# STM32_JBL_02.net
KiCad netlist of a schematic drawn in EasyEDA Pro
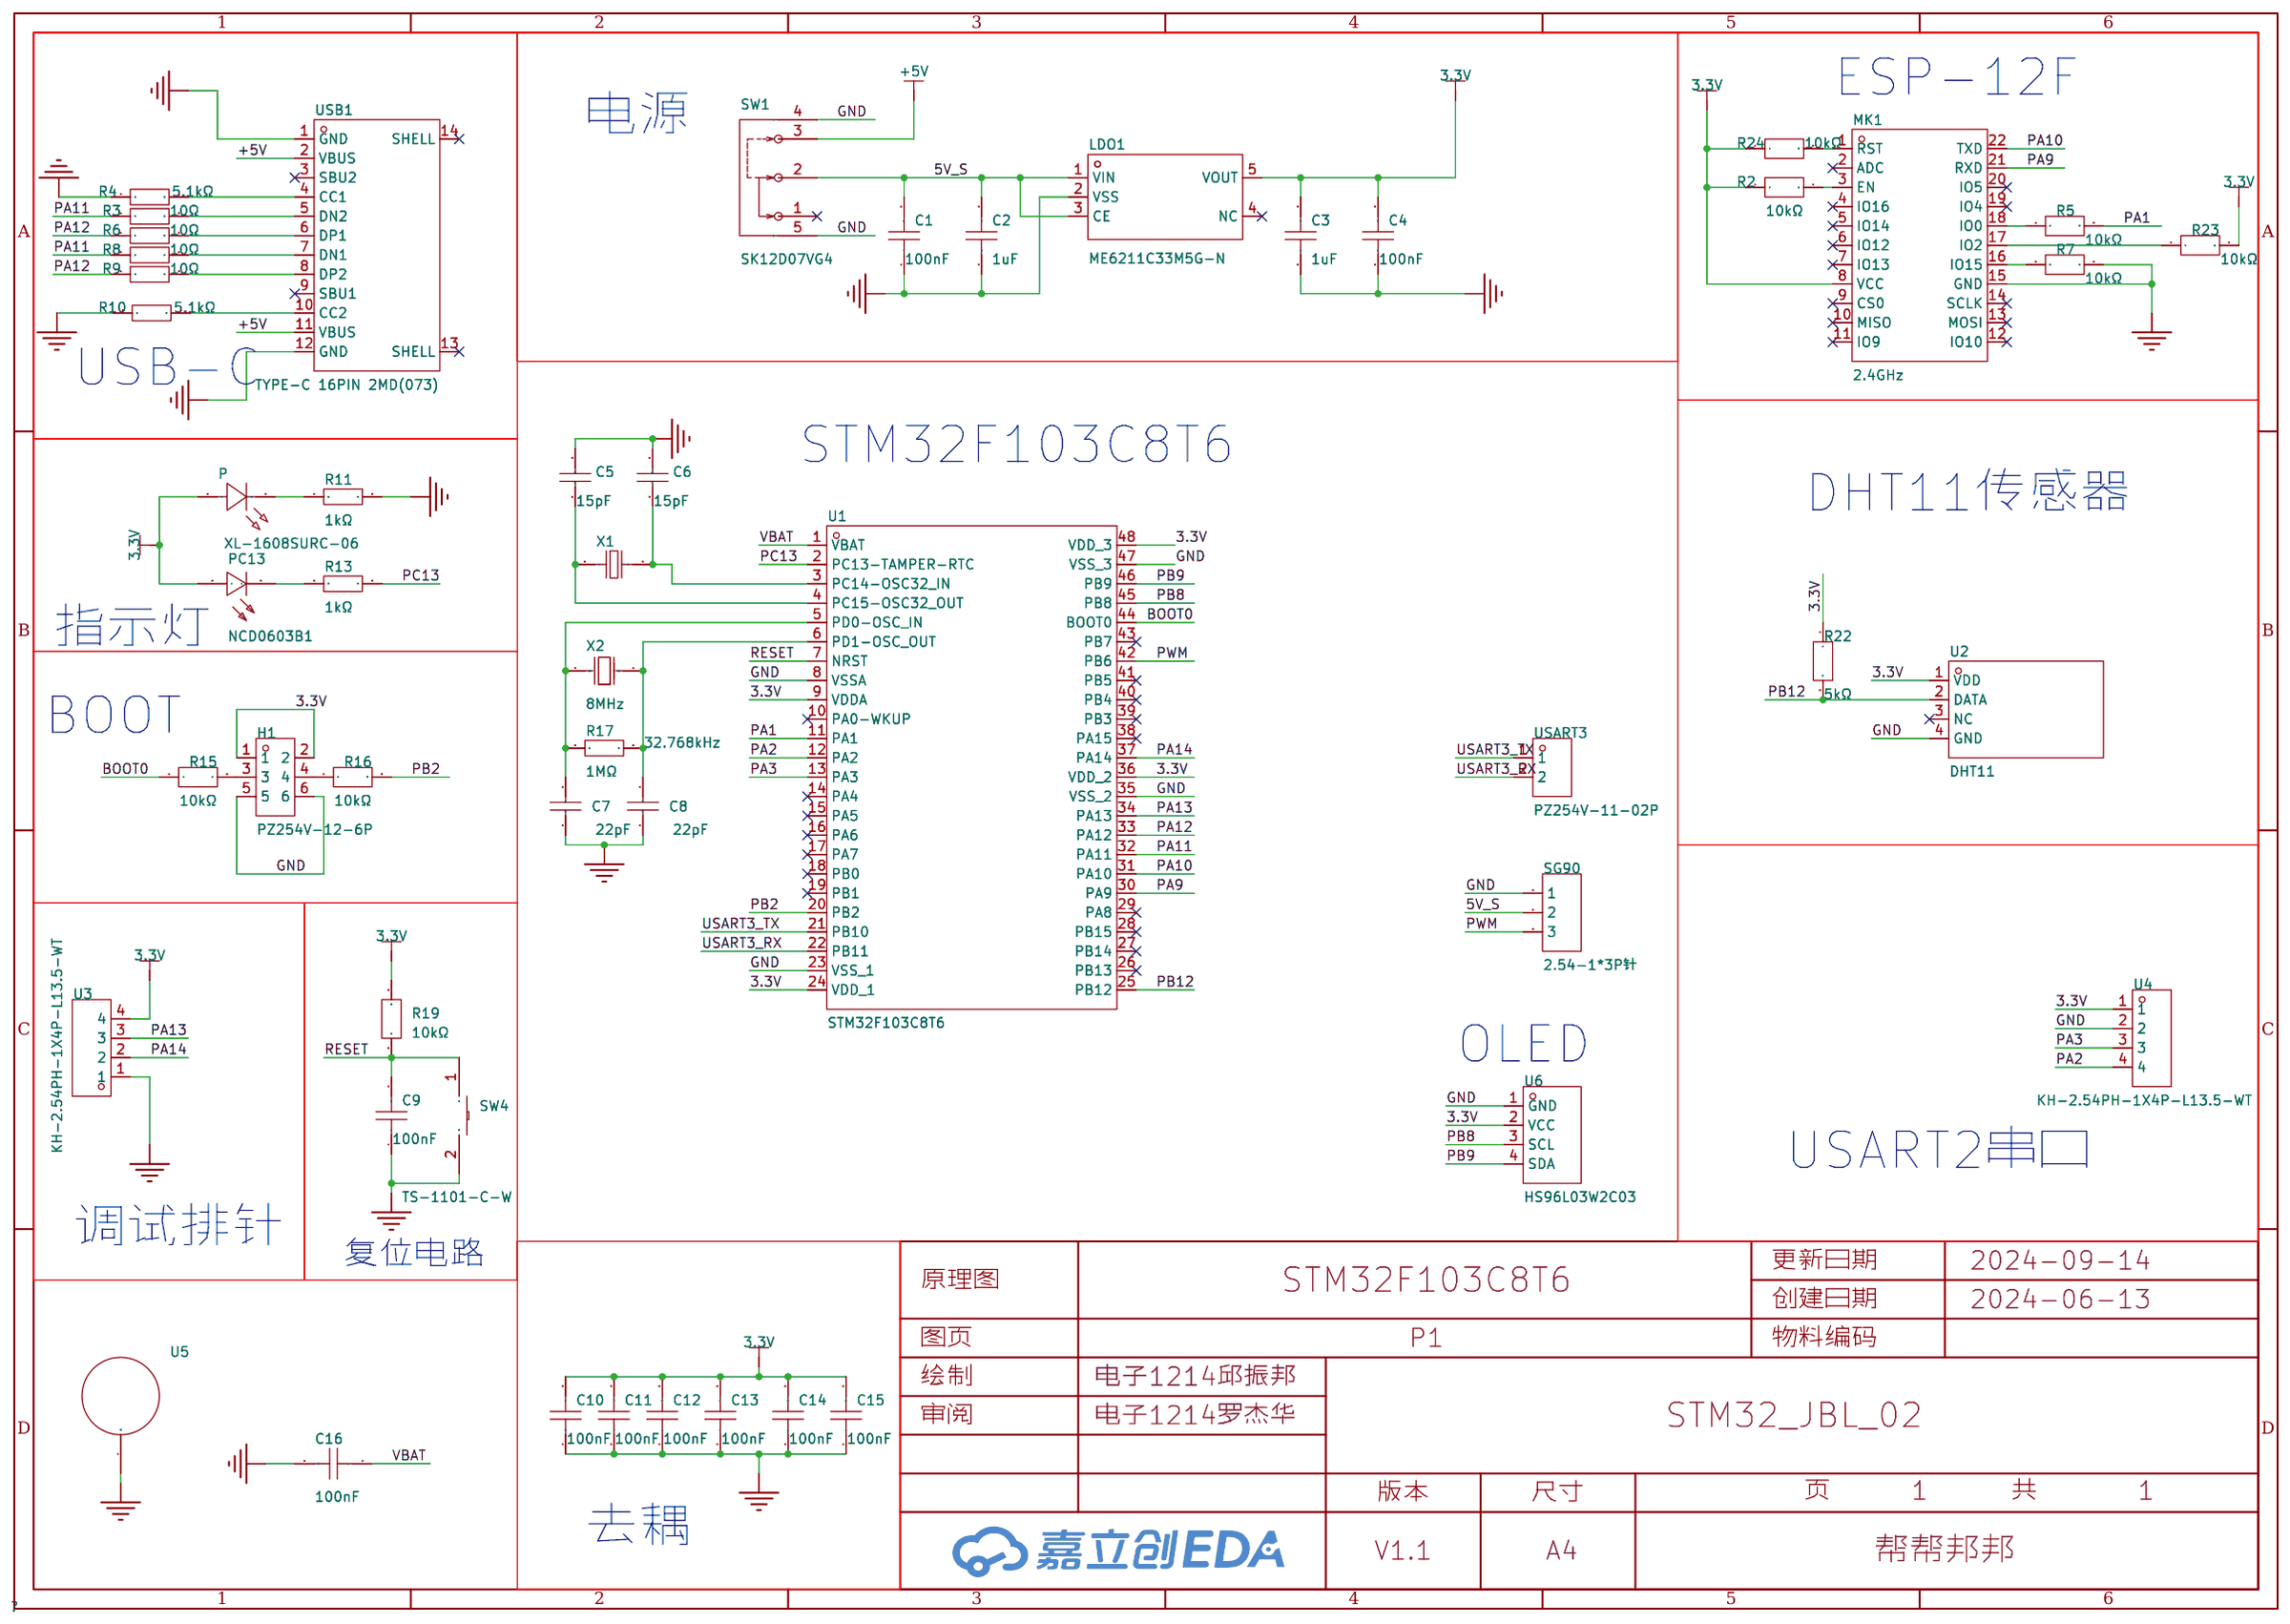
[diagram p0: schematic sheet]

(export (version "E")
  (design (tool "Eeschema 10.0.6"))
  (components
    (comp (ref "C1")
      (value "100nF")
      (footprint "easyedapro:C0603")
      (description "容值:100nF;精度:±10%;额定电压:50V;材质(温度系数):X7R;")
      (fields
        (field (name "Manufacturer Part") "CC0603KRX7R9BB104")
        (field (name "Manufacturer") "YAGEO(国巨)")
      )
      (libsource (lib "easyedapro") (part "CC0603KRX7R9BB104"))
    )
    (comp (ref "C2")
      (value "1uF")
      (footprint "easyedapro:C0603")
      (description "容值:1uF;精度:±10%;额定电压:50V;材质(温度系数):X5R;")
      (fields
        (field (name "Manufacturer Part") "CL10A105KB8NNNC")
        (field (name "Manufacturer") "SAMSUNG(三星)")
      )
      (libsource (lib "easyedapro") (part "CL10A105KB8NNNC"))
    )
    (comp (ref "C3")
      (value "1uF")
      (footprint "easyedapro:C0603")
      (description "容值:1uF;精度:±10%;额定电压:50V;材质(温度系数):X5R;")
      (fields
        (field (name "Manufacturer Part") "CL10A105KB8NNNC")
        (field (name "Manufacturer") "SAMSUNG(三星)")
      )
      (libsource (lib "easyedapro") (part "CL10A105KB8NNNC"))
    )
    (comp (ref "C4")
      (value "100nF")
      (footprint "easyedapro:C0603")
      (description "容值:100nF;精度:±10%;额定电压:50V;材质(温度系数):X7R;")
      (fields
        (field (name "Manufacturer Part") "CC0603KRX7R9BB104")
        (field (name "Manufacturer") "YAGEO(国巨)")
      )
      (libsource (lib "easyedapro") (part "CC0603KRX7R9BB104"))
    )
    (comp (ref "C5")
      (value "15pF")
      (footprint "easyedapro:C0603")
      (description "容值:15pF;精度:±5%;额定电压:50V;材质(温度系数):C0G;")
      (fields
        (field (name "Manufacturer Part") "CL10C150JB8NNNC")
        (field (name "Manufacturer") "SAMSUNG(三星)")
      )
      (libsource (lib "easyedapro") (part "CL10C150JB8NNNC"))
    )
    (comp (ref "C6")
      (value "15pF")
      (footprint "easyedapro:C0603")
      (description "容值:15pF;精度:±5%;额定电压:50V;材质(温度系数):C0G;")
      (fields
        (field (name "Manufacturer Part") "CL10C150JB8NNNC")
        (field (name "Manufacturer") "SAMSUNG(三星)")
      )
      (libsource (lib "easyedapro") (part "CL10C150JB8NNNC"))
    )
    (comp (ref "C7")
      (value "22pF")
      (footprint "easyedapro:C0603")
      (description "容值:22pF;精度:±5%;额定电压:50V;材质(温度系数):NP0;")
      (fields
        (field (name "Manufacturer Part") "CC0603JRNPO9BN220")
        (field (name "Manufacturer") "YAGEO(国巨)")
      )
      (libsource (lib "easyedapro") (part "CC0603JRNPO9BN220"))
    )
    (comp (ref "C8")
      (value "22pF")
      (footprint "easyedapro:C0603")
      (description "容值:22pF;精度:±5%;额定电压:50V;材质(温度系数):NP0;")
      (fields
        (field (name "Manufacturer Part") "CC0603JRNPO9BN220")
        (field (name "Manufacturer") "YAGEO(国巨)")
      )
      (libsource (lib "easyedapro") (part "CC0603JRNPO9BN220"))
    )
    (comp (ref "C9")
      (value "100nF")
      (footprint "easyedapro:C0603")
      (description "容值:100nF;精度:±10%;额定电压:50V;材质(温度系数):X7R;")
      (fields
        (field (name "Manufacturer Part") "CC0603KRX7R9BB104")
        (field (name "Manufacturer") "YAGEO(国巨)")
      )
      (libsource (lib "easyedapro") (part "CC0603KRX7R9BB104"))
    )
    (comp (ref "C10")
      (value "100nF")
      (footprint "easyedapro:C0603")
      (description "容值:100nF;精度:±10%;额定电压:50V;材质(温度系数):X7R;")
      (fields
        (field (name "Manufacturer Part") "CC0603KRX7R9BB104")
        (field (name "Manufacturer") "YAGEO(国巨)")
      )
      (libsource (lib "easyedapro") (part "CC0603KRX7R9BB104"))
    )
    (comp (ref "C11")
      (value "100nF")
      (footprint "easyedapro:C0603")
      (description "容值:100nF;精度:±10%;额定电压:50V;材质(温度系数):X7R;")
      (fields
        (field (name "Manufacturer Part") "CC0603KRX7R9BB104")
        (field (name "Manufacturer") "YAGEO(国巨)")
      )
      (libsource (lib "easyedapro") (part "CC0603KRX7R9BB104"))
    )
    (comp (ref "C12")
      (value "100nF")
      (footprint "easyedapro:C0603")
      (description "容值:100nF;精度:±10%;额定电压:50V;材质(温度系数):X7R;")
      (fields
        (field (name "Manufacturer Part") "CC0603KRX7R9BB104")
        (field (name "Manufacturer") "YAGEO(国巨)")
      )
      (libsource (lib "easyedapro") (part "CC0603KRX7R9BB104"))
    )
    (comp (ref "C13")
      (value "100nF")
      (footprint "easyedapro:C0603")
      (description "容值:100nF;精度:±10%;额定电压:50V;材质(温度系数):X7R;")
      (fields
        (field (name "Manufacturer Part") "CC0603KRX7R9BB104")
        (field (name "Manufacturer") "YAGEO(国巨)")
      )
      (libsource (lib "easyedapro") (part "CC0603KRX7R9BB104"))
    )
    (comp (ref "C14")
      (value "100nF")
      (footprint "easyedapro:C0603")
      (description "容值:100nF;精度:±10%;额定电压:50V;材质(温度系数):X7R;")
      (fields
        (field (name "Manufacturer Part") "CC0603KRX7R9BB104")
        (field (name "Manufacturer") "YAGEO(国巨)")
      )
      (libsource (lib "easyedapro") (part "CC0603KRX7R9BB104"))
    )
    (comp (ref "C15")
      (value "100nF")
      (footprint "easyedapro:C0603")
      (description "容值:100nF;精度:±10%;额定电压:50V;材质(温度系数):X7R;")
      (fields
        (field (name "Manufacturer Part") "CC0603KRX7R9BB104")
        (field (name "Manufacturer") "YAGEO(国巨)")
      )
      (libsource (lib "easyedapro") (part "CC0603KRX7R9BB104"))
    )
    (comp (ref "C16")
      (value "100nF")
      (footprint "easyedapro:C0603")
      (description "容值:100nF;精度:±10%;额定电压:50V;材质(温度系数):X7R;")
      (fields
        (field (name "Manufacturer Part") "CC0603KRX7R9BB104")
        (field (name "Manufacturer") "YAGEO(国巨)")
      )
      (libsource (lib "easyedapro") (part "CC0603KRX7R9BB104"))
    )
    (comp (ref "H1")
      (value "PZ254V-12-6P")
      (footprint "easyedapro:HDR-TH_6P-P2.54-V-M-R2-C3-S2.54")
      (fields (field (name "Manufacturer") "XFCN(兴飞)"))
      (libsource (lib "easyedapro") (part "PZ254V-12-6P"))
    )
    (comp (ref "LDO1")
      (value "ME6211C33M5G-N")
      (footprint "easyedapro:SOT-23-5_L3.0-W1.7-P0.95-LS2.8-BL")
      (description "输出类型:固定;最大输入电压:6V;输出电压:3.3V;最大输出电流:500mA;电源纹波抑制比(PSRR):70dB;输出极性:正极;")
      (fields (field (name "Manufacturer") "MICRONE(南京微盟)"))
      (libsource (lib "easyedapro") (part "ME6211C33M5G-N"))
    )
    (comp (ref "MK1")
      (value "2.4GHz")
      (footprint "easyedapro:WIFIM-SMD_ESP-12E-BR")
      (description "核心处理器:ESP8266芯片;频率:2.4GHz;天线形式:板载PCB天线;发射功率:16dBm;接收灵敏度:-90dBm;")
      (fields (field (name "Manufacturer Part") "ESP-12E") (field (name "Manufacturer") "Ai-Thinker(安信可)"))
      (libsource (lib "easyedapro") (part "ESP-12E"))
    )
    (comp (ref "P")
      (value "XL-1608SURC-06")
      (footprint "easyedapro:LED0603-RD_RED")
      (description "发光颜色:红色;功率:55mW;正向电流:25mA;主波长:617nm~621nm;透镜颜色:无色透明透镜;色温:-;发光角度:120°;载带方式:正贴;工作温度:-30℃~+85℃;")
      (fields (field (name "Manufacturer") "XINGLIGHT(成兴光)"))
      (libsource (lib "easyedapro") (part "XL-1608SURC-06"))
    )
    (comp (ref "PC13")
      (value "NCD0603B1")
      (footprint "easyedapro:LED0603-RD")
      (fields (field (name "Manufacturer") "国星光电"))
      (libsource (lib "easyedapro") (part "FC-DA1608BK-470H10"))
    )
    (comp (ref "R2")
      (value "10kΩ")
      (footprint "easyedapro:R0603")
      (description "电阻类型:厚膜电阻;阻值:10kΩ;精度:±5%;功率:100mW;最大工作电压:75V;温度系数:±100ppm/°C;")
      (fields (field (name "Manufacturer Part") "FRC0603J103TS") (field (name "Manufacturer") "FOJAN(富捷)"))
      (libsource (lib "easyedapro") (part "FRC0603J103TS"))
    )
    (comp (ref "R3")
      (value "10Ω")
      (footprint "easyedapro:R0603")
      (description "电阻类型:厚膜电阻;阻值:10Ω;精度:±1%;功率:100mW;最大工作电压:75V;温度系数:±400ppm/°C;")
      (fields
        (field (name "Manufacturer Part") "0603WAF100JT5E")
        (field (name "Manufacturer") "UNI-ROYAL(厚声)")
      )
      (libsource (lib "easyedapro") (part "0603WAF100JT5E"))
    )
    (comp (ref "R4")
      (value "5.1kΩ")
      (footprint "easyedapro:R0603")
      (description "电阻类型:厚膜电阻;阻值:5.1kΩ;精度:±1%;功率:100mW;最大工作电压:75V;温度系数:±100ppm/°C;")
      (fields
        (field (name "Manufacturer Part") "0603WAF5101T5E")
        (field (name "Manufacturer") "UNI-ROYAL(厚声)")
      )
      (libsource (lib "easyedapro") (part "0603WAF5101T5E"))
    )
    (comp (ref "R5")
      (value "10kΩ")
      (footprint "easyedapro:R0603")
      (description "电阻类型:厚膜电阻;阻值:10kΩ;精度:±5%;功率:100mW;最大工作电压:75V;温度系数:±100ppm/°C;")
      (fields (field (name "Manufacturer Part") "FRC0603J103TS") (field (name "Manufacturer") "FOJAN(富捷)"))
      (libsource (lib "easyedapro") (part "FRC0603J103TS"))
    )
    (comp (ref "R6")
      (value "10Ω")
      (footprint "easyedapro:R0603")
      (description "电阻类型:厚膜电阻;阻值:10Ω;精度:±1%;功率:100mW;最大工作电压:75V;温度系数:±400ppm/°C;")
      (fields
        (field (name "Manufacturer Part") "0603WAF100JT5E")
        (field (name "Manufacturer") "UNI-ROYAL(厚声)")
      )
      (libsource (lib "easyedapro") (part "0603WAF100JT5E"))
    )
    (comp (ref "R7")
      (value "10kΩ")
      (footprint "easyedapro:R0603")
      (description "电阻类型:厚膜电阻;阻值:10kΩ;精度:±5%;功率:100mW;最大工作电压:75V;温度系数:±100ppm/°C;")
      (fields (field (name "Manufacturer Part") "FRC0603J103TS") (field (name "Manufacturer") "FOJAN(富捷)"))
      (libsource (lib "easyedapro") (part "FRC0603J103TS"))
    )
    (comp (ref "R8")
      (value "10Ω")
      (footprint "easyedapro:R0603")
      (description "电阻类型:厚膜电阻;阻值:10Ω;精度:±1%;功率:100mW;最大工作电压:75V;温度系数:±400ppm/°C;")
      (fields
        (field (name "Manufacturer Part") "0603WAF100JT5E")
        (field (name "Manufacturer") "UNI-ROYAL(厚声)")
      )
      (libsource (lib "easyedapro") (part "0603WAF100JT5E"))
    )
    (comp (ref "R9")
      (value "10Ω")
      (footprint "easyedapro:R0603")
      (description "电阻类型:厚膜电阻;阻值:10Ω;精度:±1%;功率:100mW;最大工作电压:75V;温度系数:±400ppm/°C;")
      (fields
        (field (name "Manufacturer Part") "0603WAF100JT5E")
        (field (name "Manufacturer") "UNI-ROYAL(厚声)")
      )
      (libsource (lib "easyedapro") (part "0603WAF100JT5E"))
    )
    (comp (ref "R10")
      (value "5.1kΩ")
      (footprint "easyedapro:R0603")
      (description "电阻类型:厚膜电阻;阻值:5.1kΩ;精度:±1%;功率:100mW;最大工作电压:75V;温度系数:±100ppm/°C;")
      (fields
        (field (name "Manufacturer Part") "0603WAF5101T5E")
        (field (name "Manufacturer") "UNI-ROYAL(厚声)")
      )
      (libsource (lib "easyedapro") (part "0603WAF5101T5E"))
    )
    (comp (ref "R11")
      (value "1kΩ")
      (footprint "easyedapro:R0603")
      (description "电阻类型:厚膜电阻;阻值:1kΩ;精度:±1%;功率:100mW;最大工作电压:75V;温度系数:±100ppm/°C;")
      (fields (field (name "Manufacturer Part") "RC0603FR-071KL") (field (name "Manufacturer") "YAGEO(国巨)"))
      (libsource (lib "easyedapro") (part "RC0603FR-071KL"))
    )
    (comp (ref "R13")
      (value "1kΩ")
      (footprint "easyedapro:R0603")
      (description "电阻类型:厚膜电阻;阻值:1kΩ;精度:±1%;功率:100mW;最大工作电压:75V;温度系数:±100ppm/°C;")
      (fields (field (name "Manufacturer Part") "RC0603FR-071KL") (field (name "Manufacturer") "YAGEO(国巨)"))
      (libsource (lib "easyedapro") (part "RC0603FR-071KL"))
    )
    (comp (ref "R15")
      (value "10kΩ")
      (footprint "easyedapro:R0603")
      (description "电阻类型:厚膜电阻;阻值:10kΩ;精度:±5%;功率:100mW;最大工作电压:75V;温度系数:±100ppm/°C;")
      (fields (field (name "Manufacturer Part") "FRC0603J103TS") (field (name "Manufacturer") "FOJAN(富捷)"))
      (libsource (lib "easyedapro") (part "FRC0603J103TS"))
    )
    (comp (ref "R16")
      (value "10kΩ")
      (footprint "easyedapro:R0603")
      (description "电阻类型:厚膜电阻;阻值:10kΩ;精度:±5%;功率:100mW;最大工作电压:75V;温度系数:±100ppm/°C;")
      (fields (field (name "Manufacturer Part") "FRC0603J103TS") (field (name "Manufacturer") "FOJAN(富捷)"))
      (libsource (lib "easyedapro") (part "FRC0603J103TS"))
    )
    (comp (ref "R17")
      (value "1MΩ")
      (footprint "easyedapro:R0603")
      (description "电阻类型:厚膜电阻;阻值:1MΩ;精度:±1%;功率:100mW;最大工作电压:75V;温度系数:±100ppm/°C;")
      (fields
        (field (name "Manufacturer Part") "0603WAF1004T5E")
        (field (name "Manufacturer") "UNI-ROYAL(厚声)")
      )
      (libsource (lib "easyedapro") (part "0603WAF1004T5E"))
    )
    (comp (ref "R19")
      (value "10kΩ")
      (footprint "easyedapro:R0603")
      (description "电阻类型:厚膜电阻;阻值:10kΩ;精度:±5%;功率:100mW;最大工作电压:75V;温度系数:±100ppm/℃;")
      (fields (field (name "Manufacturer Part") "FRC0603J103TS") (field (name "Manufacturer") "FOJAN(富捷)"))
      (libsource (lib "easyedapro") (part "FRC0603J103TS"))
    )
    (comp (ref "R22")
      (value "5kΩ")
      (footprint "easyedapro:R0805")
      (description "电阻类型:薄膜电阻;阻值:5kΩ;精度:±0.1%;功率:125mW;最大工作电压:150V;温度系数:±25ppm/℃;")
      (fields (field (name "Manufacturer Part") "ARG05BTC5001N") (field (name "Manufacturer") "Viking(光颉)"))
      (libsource (lib "easyedapro") (part "ARG05BTC5001N"))
    )
    (comp (ref "R23")
      (value "10kΩ")
      (footprint "easyedapro:R0603")
      (description "电阻类型:厚膜电阻;阻值:10kΩ;精度:±5%;功率:100mW;最大工作电压:75V;温度系数:±100ppm/°C;")
      (fields (field (name "Manufacturer Part") "FRC0603J103TS") (field (name "Manufacturer") "FOJAN(富捷)"))
      (libsource (lib "easyedapro") (part "FRC0603J103TS"))
    )
    (comp (ref "R24")
      (value "10kΩ")
      (footprint "easyedapro:R0603")
      (description "电阻类型:厚膜电阻;阻值:10kΩ;精度:±5%;功率:100mW;最大工作电压:75V;温度系数:±100ppm/°C;")
      (fields (field (name "Manufacturer Part") "FRC0603J103TS") (field (name "Manufacturer") "FOJAN(富捷)"))
      (libsource (lib "easyedapro") (part "FRC0603J103TS"))
    )
    (comp (ref "SG90")
      (value "2.54-1*3P针")
      (footprint "easyedapro:HDR-TH_3P-P2.54-V-M-1")
      (fields (field (name "Manufacturer") "BOOMELE(博穆精密)"))
      (libsource (lib "easyedapro") (part "Header-Male-2.54_1x3"))
    )
    (comp (ref "SW1")
      (value "SK12D07VG4")
      (footprint "easyedapro:SW-TH_SK12D07VG4")
      (description "电路结构:单刀双掷;安装方式:-;额定电流(DC):500mA;额定电压(DC):50V;额定电流(AC):-;额定电压(AC):-;机械寿命:5千次;")
      (fields (field (name "Manufacturer") "SHOU HAN(首韩)"))
      (libsource (lib "easyedapro") (part "SK12D07VG4"))
    )
    (comp (ref "SW4")
      (value "TS-1101-C-W")
      (footprint "easyedapro:SW-SMD_L6.0-W3.3-LS8.0")
      (fields (field (name "Manufacturer") "XKB Connectivity(中国星坤)"))
      (libsource (lib "easyedapro") (part "TS-1101-C-W"))
    )
    (comp (ref "U1")
      (value "STM32F103C8T6")
      (footprint "easyedapro:LQFP-48_L7.0-W7.0-P0.50-LS9.0-BL")
      (description "CPU内核:ARM-M3;程序存储容量:64KB;RAM总容量:20KB;GPIO端口数量:37;工作电压范围:2V~3.6V;CPU最大主频:72MHz;程序存储器类型:FLASH;")
      (fields (field (name "Manufacturer") "ST(意法半导体)"))
      (libsource (lib "easyedapro") (part "STM32F103C8T6"))
    )
    (comp (ref "U2")
      (value "DHT11")
      (footprint "easyedapro:SENSOR-TH_DHT11")
      (description "新款电容式数字温湿度传感器,老款已停产16.1x12.6x5.8mm")
      (fields (field (name "Manufacturer") "广州奥松"))
      (libsource (lib "easyedapro") (part "DHT11"))
    )
    (comp (ref "U3")
      (value "KH-2.54PH-1X4P-L13.5-WT")
      (footprint "easyedapro:HDR-SMD_4P-P2.54-H-M-W13.3-N")
      (description "插针结构:1x4P;间距:2.54mm;安装类型:卧贴;排数:单排;")
      (fields (field (name "Manufacturer") "kinghelm(金航标)"))
      (libsource (lib "easyedapro") (part "KH-2.54PH-1X4P-L13.5-WT"))
    )
    (comp (ref "U4")
      (value "KH-2.54PH-1X4P-L13.5-WT")
      (footprint "easyedapro:HDR-SMD_4P-P2.54-H-M-W13.3-N")
      (description "插针结构:1x4P;间距:2.54mm;安装类型:卧贴;排数:单排;")
      (fields (field (name "Manufacturer") "kinghelm(金航标)"))
      (libsource (lib "easyedapro") (part "KH-2.54PH-1X4P-L13.5-WT"))
    )
    (comp (ref "U5")
      (value "~")
      (footprint "easyedapro:定位孔")
      (description "定位孔")
      (libsource (lib "easyedapro") (part "定位孔"))
    )
    (comp (ref "U6")
      (value "HS96L03W2C03")
      (footprint "easyedapro:OLED-TH_L27.8-W27.2-P2.54_C9900033791")
      (description "主控芯片:SSD1315;接口类型:I2C;尺寸(inch):0.96;像素分辨率:128x64;")
      (fields (field (name "Manufacturer") "HS(汉昇)"))
      (libsource (lib "easyedapro") (part "HS96L03W2C03"))
    )
    (comp (ref "USART3")
      (value "PZ254V-11-02P")
      (footprint "easyedapro:HDR-TH_2P-P2.54-V-M")
      (fields (field (name "Manufacturer") "XFCN(兴飞)"))
      (libsource (lib "easyedapro") (part "PZ254V-11-02P"))
    )
    (comp (ref "USB1")
      (value "TYPE-C 16PIN 2MD(073)")
      (footprint "easyedapro:USB-C-SMD_TYPE-C-6PIN-2MD-073")
      (description "连接器类型:Type-C;标准:-;公母:母;端口数量:1;触点数量:16P;安装方式:卧贴;额定电流 - 电源:5A;工作温度范围:-25°C~+85°C;")
      (fields (field (name "Manufacturer") "SHOU HAN(首韩)"))
      (libsource (lib "easyedapro") (part "TYPE-C 16PIN 2MD(073)"))
    )
    (comp (ref "X1")
      (value "32.768kHz")
      (footprint "easyedapro:FC-135R_L3.2-W1.5")
      (description "晶振类型:贴片晶振;频率:32.768kHz;常温频差:±20ppm;外接负载电容:12.5pF;")
      (fields (field (name "Manufacturer Part") "Q13FC13500004") (field (name "Manufacturer") "EPSON(爱普生)"))
      (libsource (lib "easyedapro") (part "Q13FC1350000400"))
    )
    (comp (ref "X2")
      (value "8MHz")
      (footprint "easyedapro:CRYSTAL-SMD_L11.5-W4.8-LS12.7")
      (description "晶振类型:贴片晶振;频率:8MHz;常温频差:±20ppm;外接负载电容:20pF;频率稳定度(全温):±30ppm;")
      (fields (field (name "Manufacturer Part") "X49SM8MSD2SC") (field (name "Manufacturer") "YXC(扬兴晶振)"))
      (libsource (lib "easyedapro") (part "X49SM8MSD2SC"))
    )
  )
  (nets
    (net (code "1") (name "+5V") (class "Default")
      (node (ref "SW1") (pin "3") (pinfunction "3_3") (pintype "unspecified"))
      (node (ref "USB1") (pin "11") (pinfunction "VBUS_11") (pintype "unspecified"))
      (node (ref "USB1") (pin "2") (pinfunction "VBUS_2") (pintype "unspecified"))
    )
    (net (code "2") (name "/5V_S") (class "Default")
      (node (ref "C1") (pin "2") (pinfunction "2_2") (pintype "unspecified"))
      (node (ref "C2") (pin "2") (pinfunction "2_2") (pintype "unspecified"))
      (node (ref "LDO1") (pin "1") (pinfunction "VIN_1") (pintype "input"))
      (node (ref "LDO1") (pin "3") (pinfunction "CE_3") (pintype "input"))
      (node (ref "SG90") (pin "2") (pinfunction "2_2") (pintype "input"))
      (node (ref "SW1") (pin "2") (pinfunction "2_2") (pintype "unspecified"))
    )
    (net (code "3") (name "/BOOT0") (class "Default")
      (node (ref "R15") (pin "1") (pinfunction "1_1") (pintype "unspecified"))
      (node (ref "U1") (pin "44") (pinfunction "BOOT0_44") (pintype "unspecified"))
    )
    (net (code "4") (name "/PA1") (class "Default")
      (node (ref "R5") (pin "2") (pinfunction "2_2") (pintype "unspecified"))
      (node (ref "U1") (pin "11") (pinfunction "PA1_11") (pintype "unspecified"))
    )
    (net (code "5") (name "/PA2") (class "Default")
      (node (ref "U1") (pin "12") (pinfunction "PA2_12") (pintype "unspecified"))
      (node (ref "U4") (pin "4") (pinfunction "4_4") (pintype "unspecified"))
    )
    (net (code "6") (name "/PA3") (class "Default")
      (node (ref "U1") (pin "13") (pinfunction "PA3_13") (pintype "unspecified"))
      (node (ref "U4") (pin "3") (pinfunction "3_3") (pintype "unspecified"))
    )
    (net (code "7") (name "/PA9") (class "Default")
      (node (ref "MK1") (pin "21") (pinfunction "RXD_21") (pintype "unspecified"))
      (node (ref "U1") (pin "30") (pinfunction "PA9_30") (pintype "unspecified"))
    )
    (net (code "8") (name "/PA10") (class "Default")
      (node (ref "MK1") (pin "22") (pinfunction "TXD_22") (pintype "unspecified"))
      (node (ref "U1") (pin "31") (pinfunction "PA10_31") (pintype "unspecified"))
    )
    (net (code "9") (name "/PA11") (class "Default")
      (node (ref "R3") (pin "1") (pinfunction "1_1") (pintype "input"))
      (node (ref "R8") (pin "1") (pinfunction "1_1") (pintype "input"))
      (node (ref "U1") (pin "32") (pinfunction "PA11_32") (pintype "unspecified"))
    )
    (net (code "10") (name "/PA12") (class "Default")
      (node (ref "R6") (pin "1") (pinfunction "1_1") (pintype "input"))
      (node (ref "R9") (pin "1") (pinfunction "1_1") (pintype "input"))
      (node (ref "U1") (pin "33") (pinfunction "PA12_33") (pintype "unspecified"))
    )
    (net (code "11") (name "/PA13") (class "Default")
      (node (ref "U1") (pin "34") (pinfunction "PA13_34") (pintype "unspecified"))
      (node (ref "U3") (pin "3") (pinfunction "3_3") (pintype "unspecified"))
    )
    (net (code "12") (name "/PA14") (class "Default")
      (node (ref "U1") (pin "37") (pinfunction "PA14_37") (pintype "unspecified"))
      (node (ref "U3") (pin "2") (pinfunction "2_2") (pintype "unspecified"))
    )
    (net (code "13") (name "/PB2") (class "Default")
      (node (ref "R16") (pin "2") (pinfunction "2_2") (pintype "unspecified"))
      (node (ref "U1") (pin "20") (pinfunction "PB2_20") (pintype "unspecified"))
    )
    (net (code "14") (name "/PB8") (class "Default")
      (node (ref "U1") (pin "45") (pinfunction "PB8_45") (pintype "unspecified"))
      (node (ref "U6") (pin "3") (pinfunction "SCL_3") (pintype "unspecified"))
    )
    (net (code "15") (name "/PB9") (class "Default")
      (node (ref "U1") (pin "46") (pinfunction "PB9_46") (pintype "unspecified"))
      (node (ref "U6") (pin "4") (pinfunction "SDA_4") (pintype "unspecified"))
    )
    (net (code "16") (name "/PB12") (class "Default")
      (node (ref "R22") (pin "2") (pinfunction "2_2") (pintype "unspecified"))
      (node (ref "U1") (pin "25") (pinfunction "PB12_25") (pintype "unspecified"))
      (node (ref "U2") (pin "2") (pinfunction "DATA_2") (pintype "unspecified"))
    )
    (net (code "17") (name "/PC13") (class "Default")
      (node (ref "R13") (pin "2") (pinfunction "2_2") (pintype "input"))
      (node (ref "U1") (pin "2") (pinfunction "PC13-TAMPER-RTC_2") (pintype "unspecified"))
    )
    (net (code "18") (name "/PWM") (class "Default")
      (node (ref "SG90") (pin "3") (pinfunction "3_3") (pintype "input"))
      (node (ref "U1") (pin "42") (pinfunction "PB6_42") (pintype "unspecified"))
    )
    (net (code "19") (name "/RESET") (class "Default")
      (node (ref "C9") (pin "2") (pinfunction "2_2") (pintype "unspecified"))
      (node (ref "R19") (pin "1") (pinfunction "1_1") (pintype "unspecified"))
      (node (ref "SW4") (pin "1") (pinfunction "1_1") (pintype "unspecified"))
      (node (ref "U1") (pin "7") (pinfunction "NRST_7") (pintype "unspecified"))
    )
    (net (code "20") (name "/USART3_RX") (class "Default")
      (node (ref "U1") (pin "22") (pinfunction "PB11_22") (pintype "unspecified"))
      (node (ref "USART3") (pin "2") (pinfunction "2_2") (pintype "unspecified"))
    )
    (net (code "21") (name "/USART3_TX") (class "Default")
      (node (ref "U1") (pin "21") (pinfunction "PB10_21") (pintype "unspecified"))
      (node (ref "USART3") (pin "1") (pinfunction "1_1") (pintype "unspecified"))
    )
    (net (code "22") (name "/VBAT") (class "Default")
      (node (ref "C16") (pin "1") (pinfunction "1_1") (pintype "unspecified"))
      (node (ref "U1") (pin "1") (pinfunction "VBAT_1") (pintype "unspecified"))
    )
    (net (code "23") (name "3.3V") (class "Default")
      (node (ref "C10") (pin "2") (pinfunction "2_2") (pintype "unspecified"))
      (node (ref "C11") (pin "2") (pinfunction "2_2") (pintype "unspecified"))
      (node (ref "C12") (pin "2") (pinfunction "2_2") (pintype "unspecified"))
      (node (ref "C13") (pin "2") (pinfunction "2_2") (pintype "unspecified"))
      (node (ref "C14") (pin "2") (pinfunction "2_2") (pintype "unspecified"))
      (node (ref "C15") (pin "2") (pinfunction "2_2") (pintype "unspecified"))
      (node (ref "C3") (pin "2") (pinfunction "2_2") (pintype "unspecified"))
      (node (ref "C4") (pin "2") (pinfunction "2_2") (pintype "unspecified"))
      (node (ref "H1") (pin "1") (pinfunction "1_1") (pintype "unspecified"))
      (node (ref "H1") (pin "2") (pinfunction "2_2") (pintype "unspecified"))
      (node (ref "LDO1") (pin "5") (pinfunction "VOUT_5") (pintype "input"))
      (node (ref "MK1") (pin "8") (pinfunction "VCC_8") (pintype "unspecified"))
      (node (ref "P") (pin "2") (pinfunction "A_2") (pintype "unspecified"))
      (node (ref "PC13") (pin "2") (pinfunction "+_2") (pintype "input"))
      (node (ref "R19") (pin "2") (pinfunction "2_2") (pintype "unspecified"))
      (node (ref "R2") (pin "1") (pinfunction "1_1") (pintype "unspecified"))
      (node (ref "R22") (pin "1") (pinfunction "1_1") (pintype "unspecified"))
      (node (ref "R23") (pin "2") (pinfunction "2_2") (pintype "unspecified"))
      (node (ref "R24") (pin "1") (pinfunction "1_1") (pintype "unspecified"))
      (node (ref "U1") (pin "24") (pinfunction "VDD_1_24") (pintype "unspecified"))
      (node (ref "U1") (pin "36") (pinfunction "VDD_2_36") (pintype "unspecified"))
      (node (ref "U1") (pin "48") (pinfunction "VDD_3_48") (pintype "unspecified"))
      (node (ref "U1") (pin "9") (pinfunction "VDDA_9") (pintype "unspecified"))
      (node (ref "U2") (pin "1") (pinfunction "VDD_1") (pintype "unspecified"))
      (node (ref "U3") (pin "4") (pinfunction "4_4") (pintype "unspecified"))
      (node (ref "U4") (pin "1") (pinfunction "1_1") (pintype "unspecified"))
      (node (ref "U6") (pin "2") (pinfunction "VCC_2") (pintype "unspecified"))
    )
    (net (code "24") (name "GND") (class "Default")
      (node (ref "C1") (pin "1") (pinfunction "1_1") (pintype "unspecified"))
      (node (ref "C10") (pin "1") (pinfunction "1_1") (pintype "unspecified"))
      (node (ref "C11") (pin "1") (pinfunction "1_1") (pintype "unspecified"))
      (node (ref "C12") (pin "1") (pinfunction "1_1") (pintype "unspecified"))
      (node (ref "C13") (pin "1") (pinfunction "1_1") (pintype "unspecified"))
      (node (ref "C14") (pin "1") (pinfunction "1_1") (pintype "unspecified"))
      (node (ref "C15") (pin "1") (pinfunction "1_1") (pintype "unspecified"))
      (node (ref "C16") (pin "2") (pinfunction "2_2") (pintype "unspecified"))
      (node (ref "C2") (pin "1") (pinfunction "1_1") (pintype "unspecified"))
      (node (ref "C3") (pin "1") (pinfunction "1_1") (pintype "unspecified"))
      (node (ref "C4") (pin "1") (pinfunction "1_1") (pintype "unspecified"))
      (node (ref "C5") (pin "2") (pinfunction "2_2") (pintype "input"))
      (node (ref "C6") (pin "2") (pinfunction "2_2") (pintype "input"))
      (node (ref "C7") (pin "1") (pinfunction "1_1") (pintype "input"))
      (node (ref "C8") (pin "1") (pinfunction "1_1") (pintype "input"))
      (node (ref "C9") (pin "1") (pinfunction "1_1") (pintype "unspecified"))
      (node (ref "H1") (pin "5") (pinfunction "5_5") (pintype "unspecified"))
      (node (ref "H1") (pin "6") (pinfunction "6_6") (pintype "unspecified"))
      (node (ref "LDO1") (pin "2") (pinfunction "VSS_2") (pintype "input"))
      (node (ref "MK1") (pin "15") (pinfunction "GND_15") (pintype "unspecified"))
      (node (ref "R10") (pin "1") (pinfunction "1_1") (pintype "input"))
      (node (ref "R11") (pin "2") (pinfunction "2_2") (pintype "input"))
      (node (ref "R4") (pin "1") (pinfunction "1_1") (pintype "input"))
      (node (ref "R7") (pin "2") (pinfunction "2_2") (pintype "unspecified"))
      (node (ref "SG90") (pin "1") (pinfunction "1_1") (pintype "input"))
      (node (ref "SW1") (pin "4") (pinfunction "4_4") (pintype "unspecified"))
      (node (ref "SW1") (pin "5") (pinfunction "5_5") (pintype "unspecified"))
      (node (ref "SW4") (pin "2") (pinfunction "2_2") (pintype "unspecified"))
      (node (ref "U1") (pin "23") (pinfunction "VSS_1_23") (pintype "unspecified"))
      (node (ref "U1") (pin "35") (pinfunction "VSS_2_35") (pintype "unspecified"))
      (node (ref "U1") (pin "47") (pinfunction "VSS_3_47") (pintype "unspecified"))
      (node (ref "U1") (pin "8") (pinfunction "VSSA_8") (pintype "unspecified"))
      (node (ref "U2") (pin "4") (pinfunction "GND_4") (pintype "unspecified"))
      (node (ref "U3") (pin "1") (pinfunction "1_1") (pintype "unspecified"))
      (node (ref "U4") (pin "2") (pinfunction "2_2") (pintype "unspecified"))
      (node (ref "U5") (pin "1") (pinfunction "GND_1") (pintype "bidirectional"))
      (node (ref "U6") (pin "1") (pinfunction "GND_1") (pintype "unspecified"))
      (node (ref "USB1") (pin "1") (pinfunction "GND_1") (pintype "unspecified"))
      (node (ref "USB1") (pin "12") (pinfunction "GND_12") (pintype "unspecified"))
    )
    (net (code "25") (name "Net-(H1-Pad3)") (class "Default")
      (node (ref "H1") (pin "3") (pinfunction "3_3") (pintype "unspecified"))
      (node (ref "R15") (pin "2") (pinfunction "2_2") (pintype "unspecified"))
    )
    (net (code "26") (name "Net-(H1-Pad4)") (class "Default")
      (node (ref "H1") (pin "4") (pinfunction "4_4") (pintype "unspecified"))
      (node (ref "R16") (pin "1") (pinfunction "1_1") (pintype "unspecified"))
    )
    (net (code "27") (name "Net-(MK1-EN)") (class "Default")
      (node (ref "MK1") (pin "3") (pinfunction "EN_3") (pintype "unspecified"))
      (node (ref "R2") (pin "2") (pinfunction "2_2") (pintype "unspecified"))
    )
    (net (code "28") (name "Net-(MK1-IO0)") (class "Default")
      (node (ref "MK1") (pin "18") (pinfunction "IO0_18") (pintype "unspecified"))
      (node (ref "R5") (pin "1") (pinfunction "1_1") (pintype "unspecified"))
    )
    (net (code "29") (name "Net-(MK1-IO2)") (class "Default")
      (node (ref "MK1") (pin "17") (pinfunction "IO2_17") (pintype "unspecified"))
      (node (ref "R23") (pin "1") (pinfunction "1_1") (pintype "unspecified"))
    )
    (net (code "30") (name "Net-(MK1-IO15)") (class "Default")
      (node (ref "MK1") (pin "16") (pinfunction "IO15_16") (pintype "unspecified"))
      (node (ref "R7") (pin "1") (pinfunction "1_1") (pintype "unspecified"))
    )
    (net (code "31") (name "Net-(MK1-RST)") (class "Default")
      (node (ref "MK1") (pin "1") (pinfunction "RST_1") (pintype "unspecified"))
      (node (ref "R24") (pin "2") (pinfunction "2_2") (pintype "unspecified"))
    )
    (net (code "32") (name "Net-(P-K)") (class "Default")
      (node (ref "P") (pin "1") (pinfunction "K_1") (pintype "unspecified"))
      (node (ref "R11") (pin "1") (pinfunction "1_1") (pintype "input"))
    )
    (net (code "33") (name "Net-(PC13--)") (class "Default")
      (node (ref "PC13") (pin "1") (pinfunction "-_1") (pintype "input"))
      (node (ref "R13") (pin "1") (pinfunction "1_1") (pintype "input"))
    )
    (net (code "34") (name "Net-(U1-PC14-OSC32_IN)") (class "Default")
      (node (ref "C6") (pin "1") (pinfunction "1_1") (pintype "input"))
      (node (ref "U1") (pin "3") (pinfunction "PC14-OSC32_IN_3") (pintype "unspecified"))
      (node (ref "X1") (pin "1") (pinfunction "1_1") (pintype "unspecified"))
    )
    (net (code "35") (name "Net-(U1-PC15-OSC32_OUT)") (class "Default")
      (node (ref "C5") (pin "1") (pinfunction "1_1") (pintype "input"))
      (node (ref "U1") (pin "4") (pinfunction "PC15-OSC32_OUT_4") (pintype "unspecified"))
      (node (ref "X1") (pin "2") (pinfunction "2_2") (pintype "unspecified"))
    )
    (net (code "36") (name "Net-(U1-PD0-OSC_IN)") (class "Default")
      (node (ref "C7") (pin "2") (pinfunction "2_2") (pintype "input"))
      (node (ref "R17") (pin "1") (pinfunction "1_1") (pintype "input"))
      (node (ref "U1") (pin "5") (pinfunction "PD0-OSC_IN_5") (pintype "unspecified"))
      (node (ref "X2") (pin "1") (pinfunction "OSC1_1") (pintype "input"))
    )
    (net (code "37") (name "Net-(U1-PD1-OSC_OUT)") (class "Default")
      (node (ref "C8") (pin "2") (pinfunction "2_2") (pintype "input"))
      (node (ref "R17") (pin "2") (pinfunction "2_2") (pintype "input"))
      (node (ref "U1") (pin "6") (pinfunction "PD1-OSC_OUT_6") (pintype "unspecified"))
      (node (ref "X2") (pin "2") (pinfunction "OSC2_2") (pintype "input"))
    )
    (net (code "38") (name "Net-(USB1-CC1)") (class "Default")
      (node (ref "R4") (pin "2") (pinfunction "2_2") (pintype "input"))
      (node (ref "USB1") (pin "4") (pinfunction "CC1_4") (pintype "unspecified"))
    )
    (net (code "39") (name "Net-(USB1-CC2)") (class "Default")
      (node (ref "R10") (pin "2") (pinfunction "2_2") (pintype "input"))
      (node (ref "USB1") (pin "10") (pinfunction "CC2_10") (pintype "unspecified"))
    )
    (net (code "40") (name "Net-(USB1-DN1)") (class "Default")
      (node (ref "R8") (pin "2") (pinfunction "2_2") (pintype "input"))
      (node (ref "USB1") (pin "7") (pinfunction "DN1_7") (pintype "unspecified"))
    )
    (net (code "41") (name "Net-(USB1-DN2)") (class "Default")
      (node (ref "R3") (pin "2") (pinfunction "2_2") (pintype "input"))
      (node (ref "USB1") (pin "5") (pinfunction "DN2_5") (pintype "unspecified"))
    )
    (net (code "42") (name "Net-(USB1-DP1)") (class "Default")
      (node (ref "R6") (pin "2") (pinfunction "2_2") (pintype "input"))
      (node (ref "USB1") (pin "6") (pinfunction "DP1_6") (pintype "unspecified"))
    )
    (net (code "43") (name "Net-(USB1-DP2)") (class "Default")
      (node (ref "R9") (pin "2") (pinfunction "2_2") (pintype "input"))
      (node (ref "USB1") (pin "8") (pinfunction "DP2_8") (pintype "unspecified"))
    )
    (net (code "44") (name "unconnected-(LDO1-NC-Pad4)") (class "Default")
      (node (ref "LDO1") (pin "4") (pinfunction "NC_4") (pintype "input+no_connect"))
    )
    (net (code "45") (name "unconnected-(MK1-ADC-Pad2)") (class "Default")
      (node (ref "MK1") (pin "2") (pinfunction "ADC_2") (pintype "unspecified+no_connect"))
    )
    (net (code "46") (name "unconnected-(MK1-CS0-Pad9)") (class "Default")
      (node (ref "MK1") (pin "9") (pinfunction "CS0_9") (pintype "unspecified+no_connect"))
    )
    (net (code "47") (name "unconnected-(MK1-IO4-Pad19)") (class "Default")
      (node (ref "MK1") (pin "19") (pinfunction "IO4_19") (pintype "unspecified+no_connect"))
    )
    (net (code "48") (name "unconnected-(MK1-IO5-Pad20)") (class "Default")
      (node (ref "MK1") (pin "20") (pinfunction "IO5_20") (pintype "unspecified+no_connect"))
    )
    (net (code "49") (name "unconnected-(MK1-IO9-Pad11)") (class "Default")
      (node (ref "MK1") (pin "11") (pinfunction "IO9_11") (pintype "unspecified+no_connect"))
    )
    (net (code "50") (name "unconnected-(MK1-IO10-Pad12)") (class "Default")
      (node (ref "MK1") (pin "12") (pinfunction "IO10_12") (pintype "unspecified+no_connect"))
    )
    (net (code "51") (name "unconnected-(MK1-IO12-Pad6)") (class "Default")
      (node (ref "MK1") (pin "6") (pinfunction "IO12_6") (pintype "unspecified+no_connect"))
    )
    (net (code "52") (name "unconnected-(MK1-IO13-Pad7)") (class "Default")
      (node (ref "MK1") (pin "7") (pinfunction "IO13_7") (pintype "unspecified+no_connect"))
    )
    (net (code "53") (name "unconnected-(MK1-IO14-Pad5)") (class "Default")
      (node (ref "MK1") (pin "5") (pinfunction "IO14_5") (pintype "unspecified+no_connect"))
    )
    (net (code "54") (name "unconnected-(MK1-IO16-Pad4)") (class "Default")
      (node (ref "MK1") (pin "4") (pinfunction "IO16_4") (pintype "unspecified+no_connect"))
    )
    (net (code "55") (name "unconnected-(MK1-MISO-Pad10)") (class "Default")
      (node (ref "MK1") (pin "10") (pinfunction "MISO_10") (pintype "unspecified+no_connect"))
    )
    (net (code "56") (name "unconnected-(MK1-MOSI-Pad13)") (class "Default")
      (node (ref "MK1") (pin "13") (pinfunction "MOSI_13") (pintype "unspecified+no_connect"))
    )
    (net (code "57") (name "unconnected-(MK1-SCLK-Pad14)") (class "Default")
      (node (ref "MK1") (pin "14") (pinfunction "SCLK_14") (pintype "unspecified+no_connect"))
    )
    (net (code "58") (name "unconnected-(SW1-Pad1)") (class "Default")
      (node (ref "SW1") (pin "1") (pinfunction "1_1") (pintype "unspecified+no_connect"))
    )
    (net (code "59") (name "unconnected-(U1-PA0-WKUP-Pad10)") (class "Default")
      (node (ref "U1") (pin "10") (pinfunction "PA0-WKUP_10") (pintype "unspecified+no_connect"))
    )
    (net (code "60") (name "unconnected-(U1-PA4-Pad14)") (class "Default")
      (node (ref "U1") (pin "14") (pinfunction "PA4_14") (pintype "unspecified+no_connect"))
    )
    (net (code "61") (name "unconnected-(U1-PA5-Pad15)") (class "Default")
      (node (ref "U1") (pin "15") (pinfunction "PA5_15") (pintype "unspecified+no_connect"))
    )
    (net (code "62") (name "unconnected-(U1-PA6-Pad16)") (class "Default")
      (node (ref "U1") (pin "16") (pinfunction "PA6_16") (pintype "unspecified+no_connect"))
    )
    (net (code "63") (name "unconnected-(U1-PA7-Pad17)") (class "Default")
      (node (ref "U1") (pin "17") (pinfunction "PA7_17") (pintype "unspecified+no_connect"))
    )
    (net (code "64") (name "unconnected-(U1-PA8-Pad29)") (class "Default")
      (node (ref "U1") (pin "29") (pinfunction "PA8_29") (pintype "unspecified+no_connect"))
    )
    (net (code "65") (name "unconnected-(U1-PA15-Pad38)") (class "Default")
      (node (ref "U1") (pin "38") (pinfunction "PA15_38") (pintype "unspecified+no_connect"))
    )
    (net (code "66") (name "unconnected-(U1-PB0-Pad18)") (class "Default")
      (node (ref "U1") (pin "18") (pinfunction "PB0_18") (pintype "unspecified+no_connect"))
    )
    (net (code "67") (name "unconnected-(U1-PB1-Pad19)") (class "Default")
      (node (ref "U1") (pin "19") (pinfunction "PB1_19") (pintype "unspecified+no_connect"))
    )
    (net (code "68") (name "unconnected-(U1-PB3-Pad39)") (class "Default")
      (node (ref "U1") (pin "39") (pinfunction "PB3_39") (pintype "unspecified+no_connect"))
    )
    (net (code "69") (name "unconnected-(U1-PB4-Pad40)") (class "Default")
      (node (ref "U1") (pin "40") (pinfunction "PB4_40") (pintype "unspecified+no_connect"))
    )
    (net (code "70") (name "unconnected-(U1-PB5-Pad41)") (class "Default")
      (node (ref "U1") (pin "41") (pinfunction "PB5_41") (pintype "unspecified+no_connect"))
    )
    (net (code "71") (name "unconnected-(U1-PB7-Pad43)") (class "Default")
      (node (ref "U1") (pin "43") (pinfunction "PB7_43") (pintype "unspecified+no_connect"))
    )
    (net (code "72") (name "unconnected-(U1-PB13-Pad26)") (class "Default")
      (node (ref "U1") (pin "26") (pinfunction "PB13_26") (pintype "unspecified+no_connect"))
    )
    (net (code "73") (name "unconnected-(U1-PB14-Pad27)") (class "Default")
      (node (ref "U1") (pin "27") (pinfunction "PB14_27") (pintype "unspecified+no_connect"))
    )
    (net (code "74") (name "unconnected-(U1-PB15-Pad28)") (class "Default")
      (node (ref "U1") (pin "28") (pinfunction "PB15_28") (pintype "unspecified+no_connect"))
    )
    (net (code "75") (name "unconnected-(U2-NC-Pad3)") (class "Default")
      (node (ref "U2") (pin "3") (pinfunction "NC_3") (pintype "unspecified+no_connect"))
    )
    (net (code "76") (name "unconnected-(USB1-SBU1-Pad9)") (class "Default")
      (node (ref "USB1") (pin "9") (pinfunction "SBU1_9") (pintype "unspecified+no_connect"))
    )
    (net (code "77") (name "unconnected-(USB1-SBU2-Pad3)") (class "Default")
      (node (ref "USB1") (pin "3") (pinfunction "SBU2_3") (pintype "unspecified+no_connect"))
    )
    (net (code "78") (name "unconnected-(USB1-SHELL-Pad13)") (class "Default")
      (node (ref "USB1") (pin "13") (pinfunction "SHELL_13") (pintype "unspecified+no_connect"))
    )
    (net (code "79") (name "unconnected-(USB1-SHELL-Pad14)") (class "Default")
      (node (ref "USB1") (pin "14") (pinfunction "SHELL_14") (pintype "unspecified+no_connect"))
    )
  )
)
